# 1-Schematic_syntheseproject_planA.net
KiCad netlist of a schematic drawn in EasyEDA
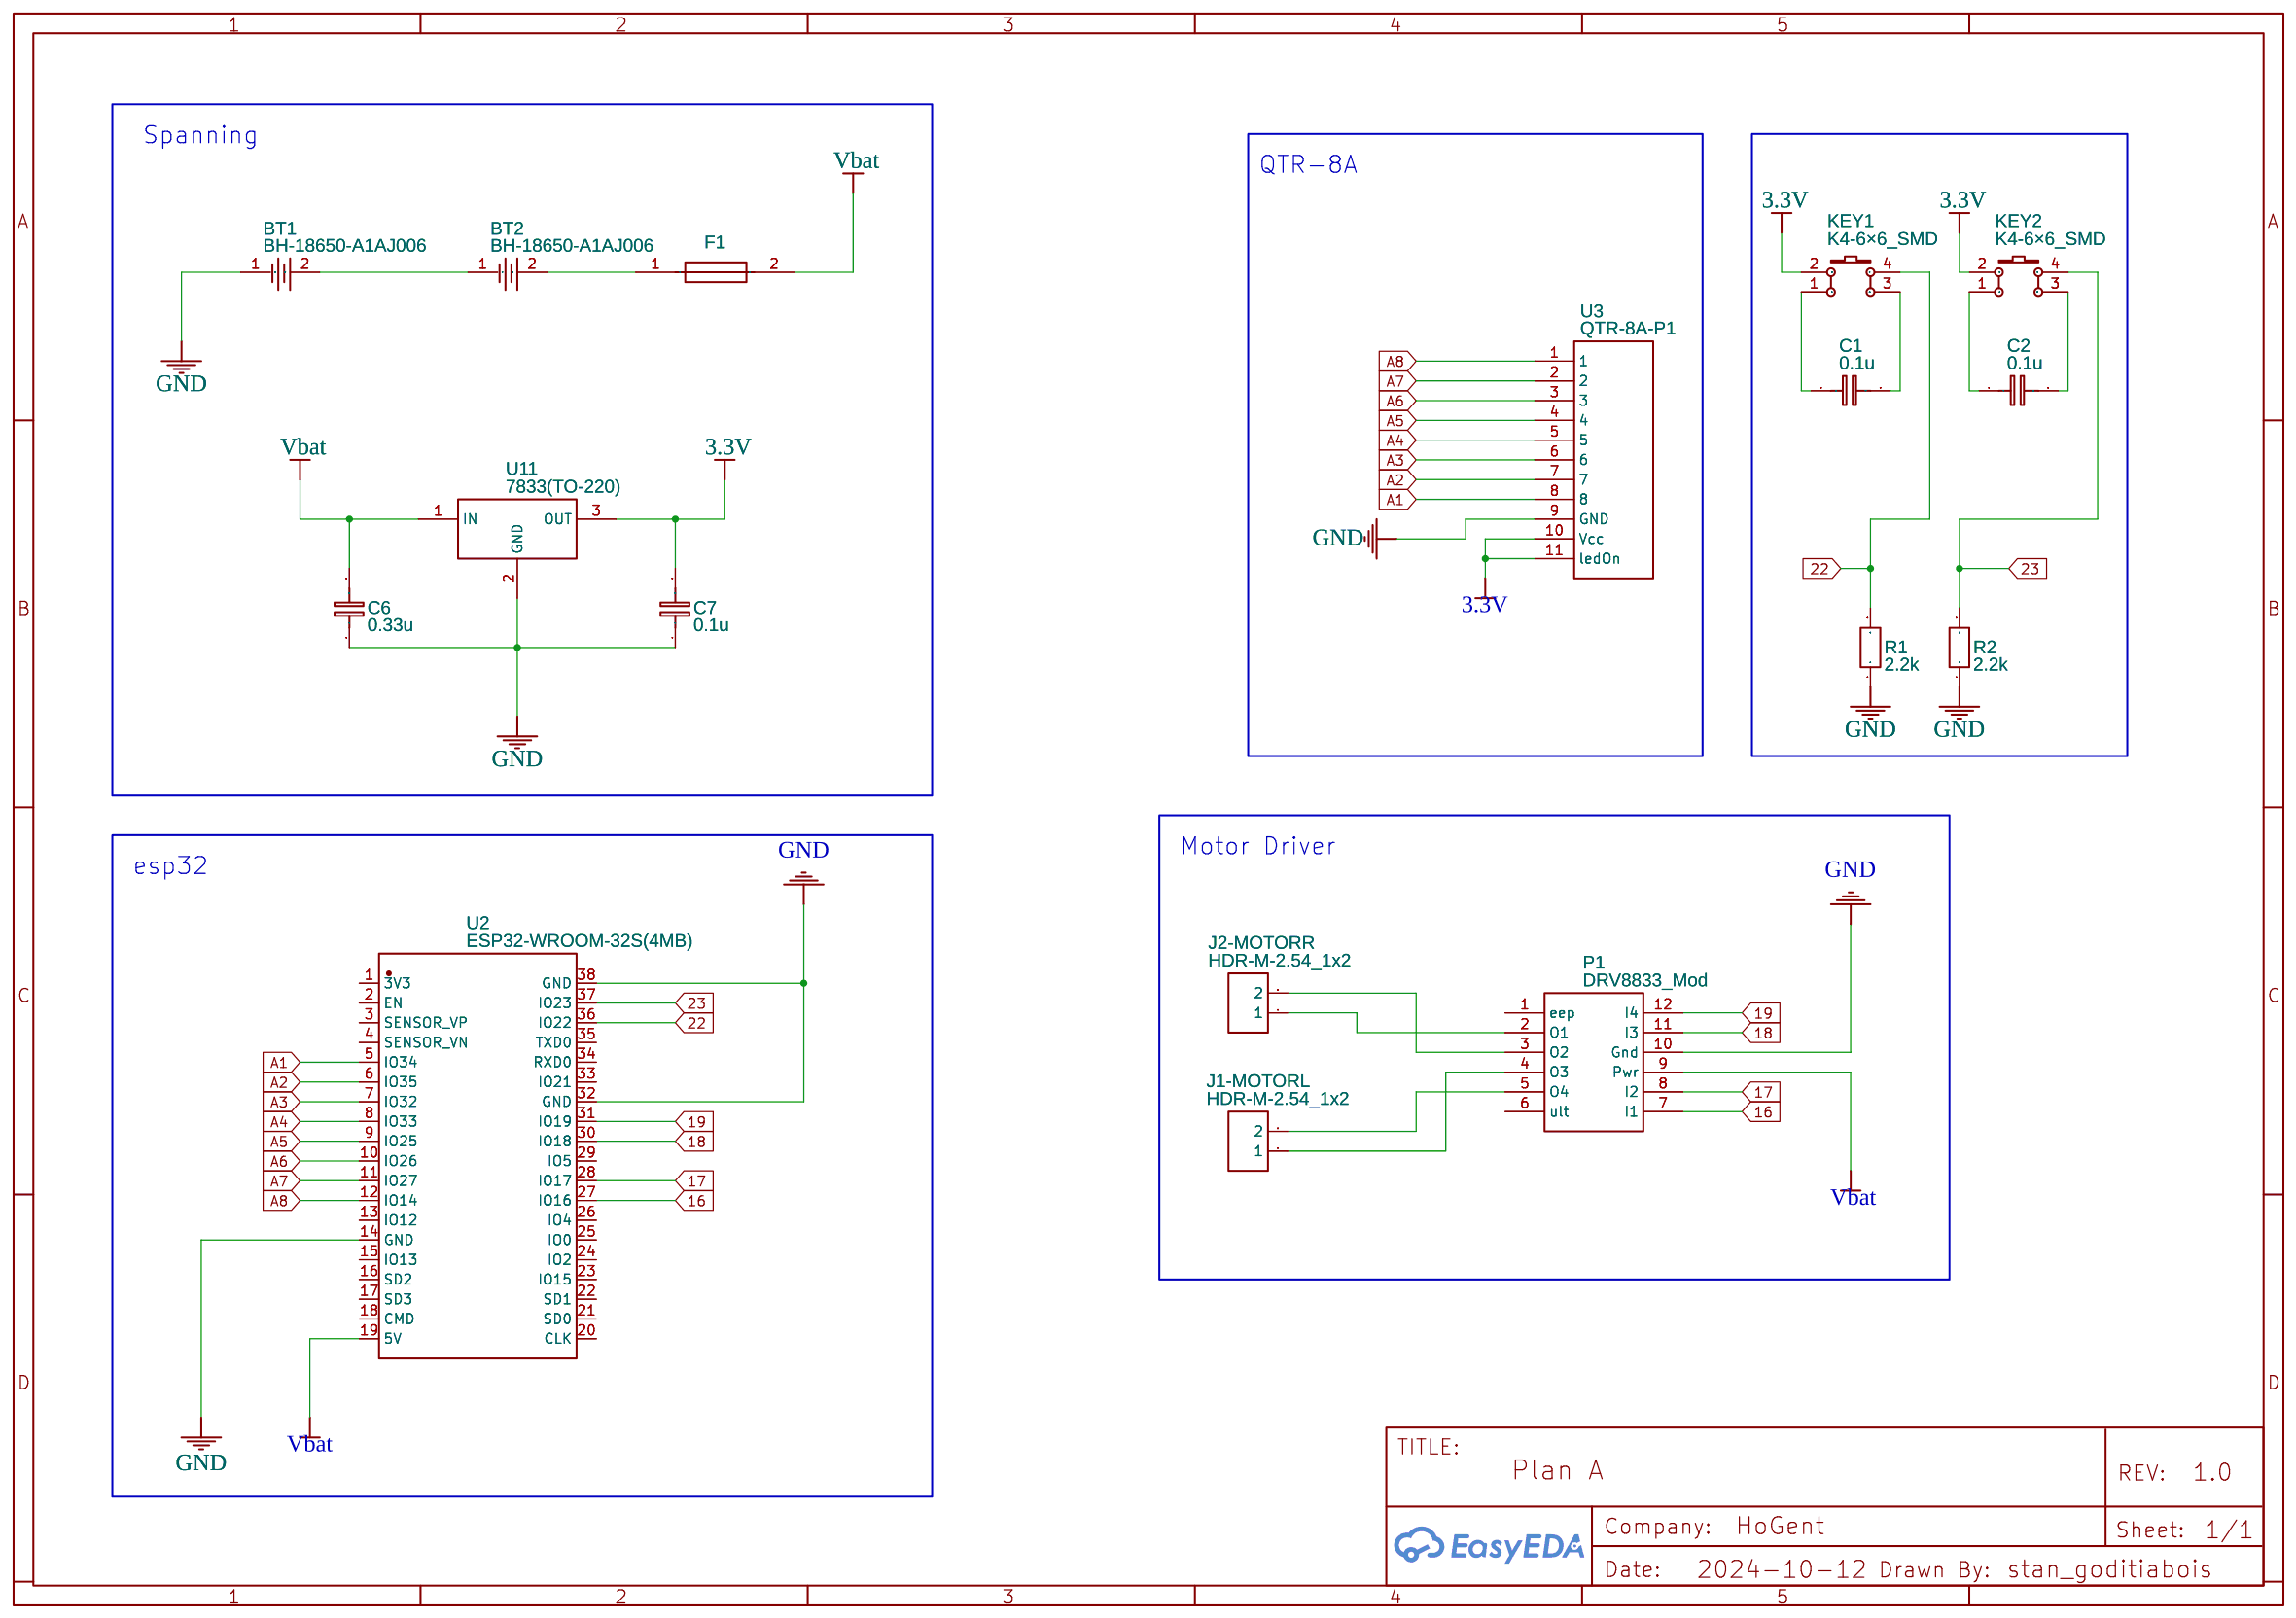
[diagram p0: schematic sheet]

(export (version "E")
  (design (tool "Eeschema 10.0.6"))
  (components
    (comp (ref "BT1")
      (value "BH-18650-A1AJ006")
      (fields (field (name "Manufacturer") "MYOUNG(美阳)"))
      (libsource (lib "") (part "BH-18650-A1AJ006"))
    )
    (comp (ref "BT2")
      (value "BH-18650-A1AJ006")
      (fields (field (name "Manufacturer") "MYOUNG(美阳)"))
      (libsource (lib "") (part "BH-18650-A1AJ006"))
    )
    (comp (ref "C1") (value "0.1u") (libsource (lib "") (part "C_0603_EU")))
    (comp (ref "C2") (value "0.1u") (libsource (lib "") (part "C_0603_EU")))
    (comp (ref "C6") (value "0.33u") (libsource (lib "") (part "C_0805_EU")))
    (comp (ref "C7") (value "0.1u") (libsource (lib "") (part "C_0805_EU")))
    (comp (ref "F1")
      (value "JK600-150U")
      (fields (field (name "Manufacturer") "Yenji"))
      (libsource (lib "") (part "JK600-150U"))
    )
    (comp (ref "J1-MOTORL") (value "HDR-M-2.54_1x2") (libsource (lib "") (part "HDR-M-2.54_1x2_1")))
    (comp (ref "J2-MOTORR") (value "HDR-M-2.54_1x2") (libsource (lib "") (part "HDR-M-2.54_1x2")))
    (comp (ref "KEY1")
      (value "K4-6×6_SMD")
      (fields (field (name "Manufacturer Part") "K2-6639SP-D4SC-04") (field (name "Manufacturer") "韩国韩荣"))
      (libsource (lib "") (part "K4-6×6_SMD"))
    )
    (comp (ref "KEY2")
      (value "K4-6×6_SMD")
      (fields (field (name "Manufacturer Part") "K2-6639SP-D4SC-04") (field (name "Manufacturer") "韩国韩荣"))
      (libsource (lib "") (part "K4-6×6_SMD"))
    )
    (comp (ref "P1") (value "DRV8833_Mod") (libsource (lib "") (part "DRV8833_Mod")))
    (comp (ref "R1") (value "2.2k") (libsource (lib "") (part "R_0805_EU")))
    (comp (ref "R2") (value "2.2k") (libsource (lib "") (part "R_0805_EU")))
    (comp (ref "U2")
      (value "ESP32-WROOM-32S(4MB)")
      (fields (field (name "Manufacturer") "Espressif Systems"))
      (libsource (lib "") (part "ESP32-WROOM-32S(4MB)"))
    )
    (comp (ref "U3") (value "QTR-8A-P1") (libsource (lib "") (part "QTR-8A-P1")))
    (comp (ref "U11")
      (value "7833(TO-220)")
      (fields
        (field (name "Manufacturer Part") "LM7833-TA3-I-T")
        (field (name "Manufacturer") "Taitron Components Incorporated")
      )
      (libsource (lib "") (part "7833(TO-220)"))
    )
  )
  (nets
    (net (code "1") (name "3.3V") (class "Default")
      (node (ref "C7") (pin "2") (pinfunction "2_2") (pintype "unspecified"))
      (node (ref "KEY1") (pin "2") (pinfunction "2_2") (pintype "unspecified"))
      (node (ref "KEY2") (pin "2") (pinfunction "2_2") (pintype "unspecified"))
      (node (ref "U11") (pin "3") (pinfunction "OUT_3") (pintype "passive"))
      (node (ref "U3") (pin "10") (pinfunction "Vcc_10") (pintype "unspecified"))
      (node (ref "U3") (pin "11") (pinfunction "ledOn_11") (pintype "unspecified"))
    )
    (net (code "2") (name "16") (class "Default")
      (node (ref "P1") (pin "7") (pinfunction "I1_7") (pintype "unspecified"))
      (node (ref "U2") (pin "27") (pinfunction "IO16_27") (pintype "unspecified"))
    )
    (net (code "3") (name "17") (class "Default")
      (node (ref "P1") (pin "8") (pinfunction "I2_8") (pintype "unspecified"))
      (node (ref "U2") (pin "28") (pinfunction "IO17_28") (pintype "unspecified"))
    )
    (net (code "4") (name "18") (class "Default")
      (node (ref "P1") (pin "11") (pinfunction "I3_11") (pintype "unspecified"))
      (node (ref "U2") (pin "30") (pinfunction "IO18_30") (pintype "unspecified"))
    )
    (net (code "5") (name "19") (class "Default")
      (node (ref "P1") (pin "12") (pinfunction "I4_12") (pintype "unspecified"))
      (node (ref "U2") (pin "31") (pinfunction "IO19_31") (pintype "unspecified"))
    )
    (net (code "6") (name "22") (class "Default")
      (node (ref "KEY1") (pin "4") (pinfunction "4_4") (pintype "unspecified"))
      (node (ref "R1") (pin "2") (pinfunction "2_2") (pintype "unspecified"))
      (node (ref "U2") (pin "36") (pinfunction "IO22_36") (pintype "unspecified"))
    )
    (net (code "7") (name "23") (class "Default")
      (node (ref "KEY2") (pin "4") (pinfunction "4_4") (pintype "unspecified"))
      (node (ref "R2") (pin "2") (pinfunction "2_2") (pintype "unspecified"))
      (node (ref "U2") (pin "37") (pinfunction "IO23_37") (pintype "unspecified"))
    )
    (net (code "8") (name "A1") (class "Default")
      (node (ref "U2") (pin "5") (pinfunction "IO34_5") (pintype "unspecified"))
      (node (ref "U3") (pin "8") (pinfunction "8_8") (pintype "unspecified"))
    )
    (net (code "9") (name "A2") (class "Default")
      (node (ref "U2") (pin "6") (pinfunction "IO35_6") (pintype "unspecified"))
      (node (ref "U3") (pin "7") (pinfunction "7_7") (pintype "unspecified"))
    )
    (net (code "10") (name "A3") (class "Default")
      (node (ref "U2") (pin "7") (pinfunction "IO32_7") (pintype "unspecified"))
      (node (ref "U3") (pin "6") (pinfunction "6_6") (pintype "unspecified"))
    )
    (net (code "11") (name "A4") (class "Default")
      (node (ref "U2") (pin "8") (pinfunction "IO33_8") (pintype "unspecified"))
      (node (ref "U3") (pin "5") (pinfunction "5_5") (pintype "unspecified"))
    )
    (net (code "12") (name "A5") (class "Default")
      (node (ref "U2") (pin "9") (pinfunction "IO25_9") (pintype "unspecified"))
      (node (ref "U3") (pin "4") (pinfunction "4_4") (pintype "unspecified"))
    )
    (net (code "13") (name "A6") (class "Default")
      (node (ref "U2") (pin "10") (pinfunction "IO26_10") (pintype "unspecified"))
      (node (ref "U3") (pin "3") (pinfunction "3_3") (pintype "unspecified"))
    )
    (net (code "14") (name "A7") (class "Default")
      (node (ref "U2") (pin "11") (pinfunction "IO27_11") (pintype "unspecified"))
      (node (ref "U3") (pin "2") (pinfunction "2_2") (pintype "unspecified"))
    )
    (net (code "15") (name "A8") (class "Default")
      (node (ref "U2") (pin "12") (pinfunction "IO14_12") (pintype "unspecified"))
      (node (ref "U3") (pin "1") (pinfunction "1_1") (pintype "unspecified"))
    )
    (net (code "16") (name "GND") (class "Default")
      (node (ref "BT1") (pin "1") (pinfunction "1_1") (pintype "input"))
      (node (ref "C6") (pin "1") (pinfunction "1_1") (pintype "unspecified"))
      (node (ref "C7") (pin "1") (pinfunction "1_1") (pintype "unspecified"))
      (node (ref "P1") (pin "10") (pinfunction "Gnd_10") (pintype "unspecified"))
      (node (ref "R1") (pin "1") (pinfunction "1_1") (pintype "unspecified"))
      (node (ref "R2") (pin "1") (pinfunction "1_1") (pintype "unspecified"))
      (node (ref "U11") (pin "2") (pinfunction "GND_2") (pintype "passive"))
      (node (ref "U2") (pin "14") (pinfunction "GND_14") (pintype "unspecified"))
      (node (ref "U2") (pin "32") (pinfunction "GND_32") (pintype "unspecified"))
      (node (ref "U2") (pin "38") (pinfunction "GND_38") (pintype "unspecified"))
      (node (ref "U3") (pin "9") (pinfunction "GND_9") (pintype "unspecified"))
    )
    (net (code "17") (name "Net-(BT1-Pad2)") (class "Default")
      (node (ref "BT1") (pin "2") (pinfunction "2_2") (pintype "input"))
      (node (ref "BT2") (pin "1") (pinfunction "1_1") (pintype "input"))
    )
    (net (code "18") (name "Net-(BT2-Pad2)") (class "Default")
      (node (ref "BT2") (pin "2") (pinfunction "2_2") (pintype "input"))
      (node (ref "F1") (pin "1") (pinfunction "1_1") (pintype "unspecified"))
    )
    (net (code "19") (name "Net-(C1-Pad1)") (class "Default")
      (node (ref "C1") (pin "1") (pinfunction "1_1") (pintype "unspecified"))
      (node (ref "KEY1") (pin "1") (pinfunction "1_1") (pintype "unspecified"))
    )
    (net (code "20") (name "Net-(C1-Pad2)") (class "Default")
      (node (ref "C1") (pin "2") (pinfunction "2_2") (pintype "unspecified"))
      (node (ref "KEY1") (pin "3") (pinfunction "3_3") (pintype "unspecified"))
    )
    (net (code "21") (name "Net-(C2-Pad1)") (class "Default")
      (node (ref "C2") (pin "1") (pinfunction "1_1") (pintype "unspecified"))
      (node (ref "KEY2") (pin "1") (pinfunction "1_1") (pintype "unspecified"))
    )
    (net (code "22") (name "Net-(C2-Pad2)") (class "Default")
      (node (ref "C2") (pin "2") (pinfunction "2_2") (pintype "unspecified"))
      (node (ref "KEY2") (pin "3") (pinfunction "3_3") (pintype "unspecified"))
    )
    (net (code "23") (name "Net-(P1-O1)") (class "Default")
      (node (ref "J2-MOTORR") (pin "1") (pinfunction "1_1") (pintype "unspecified"))
      (node (ref "P1") (pin "2") (pinfunction "O1_2") (pintype "unspecified"))
    )
    (net (code "24") (name "Net-(P1-O2)") (class "Default")
      (node (ref "J2-MOTORR") (pin "2") (pinfunction "2_2") (pintype "unspecified"))
      (node (ref "P1") (pin "3") (pinfunction "O2_3") (pintype "unspecified"))
    )
    (net (code "25") (name "Net-(P1-O3)") (class "Default")
      (node (ref "J1-MOTORL") (pin "1") (pinfunction "1_1") (pintype "unspecified"))
      (node (ref "P1") (pin "4") (pinfunction "O3_4") (pintype "unspecified"))
    )
    (net (code "26") (name "Net-(P1-O4)") (class "Default")
      (node (ref "J1-MOTORL") (pin "2") (pinfunction "2_2") (pintype "unspecified"))
      (node (ref "P1") (pin "5") (pinfunction "O4_5") (pintype "unspecified"))
    )
    (net (code "27") (name "Vbat") (class "Default")
      (node (ref "C6") (pin "2") (pinfunction "2_2") (pintype "unspecified"))
      (node (ref "F1") (pin "2") (pinfunction "2_2") (pintype "unspecified"))
      (node (ref "P1") (pin "9") (pinfunction "Pwr_9") (pintype "unspecified"))
      (node (ref "U11") (pin "1") (pinfunction "IN_1") (pintype "passive"))
      (node (ref "U2") (pin "19") (pinfunction "5V_19") (pintype "unspecified"))
    )
    (net (code "28") (name "unconnected-(P1-eep-Pad1)") (class "Default")
      (node (ref "P1") (pin "1") (pinfunction "eep_1") (pintype "unspecified"))
    )
    (net (code "29") (name "unconnected-(P1-ult-Pad6)") (class "Default")
      (node (ref "P1") (pin "6") (pinfunction "ult_6") (pintype "unspecified"))
    )
    (net (code "30") (name "unconnected-(U2-3V3-Pad1)") (class "Default")
      (node (ref "U2") (pin "1") (pinfunction "3V3_1") (pintype "unspecified"))
    )
    (net (code "31") (name "unconnected-(U2-CLK-Pad20)") (class "Default")
      (node (ref "U2") (pin "20") (pinfunction "CLK_20") (pintype "unspecified"))
    )
    (net (code "32") (name "unconnected-(U2-CMD-Pad18)") (class "Default")
      (node (ref "U2") (pin "18") (pinfunction "CMD_18") (pintype "unspecified"))
    )
    (net (code "33") (name "unconnected-(U2-EN-Pad2)") (class "Default")
      (node (ref "U2") (pin "2") (pinfunction "EN_2") (pintype "unspecified"))
    )
    (net (code "34") (name "unconnected-(U2-IO0-Pad25)") (class "Default")
      (node (ref "U2") (pin "25") (pinfunction "IO0_25") (pintype "unspecified"))
    )
    (net (code "35") (name "unconnected-(U2-IO2-Pad24)") (class "Default")
      (node (ref "U2") (pin "24") (pinfunction "IO2_24") (pintype "unspecified"))
    )
    (net (code "36") (name "unconnected-(U2-IO4-Pad26)") (class "Default")
      (node (ref "U2") (pin "26") (pinfunction "IO4_26") (pintype "unspecified"))
    )
    (net (code "37") (name "unconnected-(U2-IO5-Pad29)") (class "Default")
      (node (ref "U2") (pin "29") (pinfunction "IO5_29") (pintype "unspecified"))
    )
    (net (code "38") (name "unconnected-(U2-IO12-Pad13)") (class "Default")
      (node (ref "U2") (pin "13") (pinfunction "IO12_13") (pintype "unspecified"))
    )
    (net (code "39") (name "unconnected-(U2-IO13-Pad15)") (class "Default")
      (node (ref "U2") (pin "15") (pinfunction "IO13_15") (pintype "unspecified"))
    )
    (net (code "40") (name "unconnected-(U2-IO15-Pad23)") (class "Default")
      (node (ref "U2") (pin "23") (pinfunction "IO15_23") (pintype "unspecified"))
    )
    (net (code "41") (name "unconnected-(U2-IO21-Pad33)") (class "Default")
      (node (ref "U2") (pin "33") (pinfunction "IO21_33") (pintype "unspecified"))
    )
    (net (code "42") (name "unconnected-(U2-RXD0-Pad34)") (class "Default")
      (node (ref "U2") (pin "34") (pinfunction "RXD0_34") (pintype "unspecified"))
    )
    (net (code "43") (name "unconnected-(U2-SD0-Pad21)") (class "Default")
      (node (ref "U2") (pin "21") (pinfunction "SD0_21") (pintype "unspecified"))
    )
    (net (code "44") (name "unconnected-(U2-SD1-Pad22)") (class "Default")
      (node (ref "U2") (pin "22") (pinfunction "SD1_22") (pintype "unspecified"))
    )
    (net (code "45") (name "unconnected-(U2-SD2-Pad16)") (class "Default")
      (node (ref "U2") (pin "16") (pinfunction "SD2_16") (pintype "unspecified"))
    )
    (net (code "46") (name "unconnected-(U2-SD3-Pad17)") (class "Default")
      (node (ref "U2") (pin "17") (pinfunction "SD3_17") (pintype "unspecified"))
    )
    (net (code "47") (name "unconnected-(U2-SENSOR_VN-Pad4)") (class "Default")
      (node (ref "U2") (pin "4") (pinfunction "SENSOR_VN_4") (pintype "unspecified"))
    )
    (net (code "48") (name "unconnected-(U2-SENSOR_VP-Pad3)") (class "Default")
      (node (ref "U2") (pin "3") (pinfunction "SENSOR_VP_3") (pintype "unspecified"))
    )
    (net (code "49") (name "unconnected-(U2-TXD0-Pad35)") (class "Default")
      (node (ref "U2") (pin "35") (pinfunction "TXD0_35") (pintype "unspecified"))
    )
  )
)
